# FSK_test.net
KiCad netlist of a schematic drawn in EAGLE
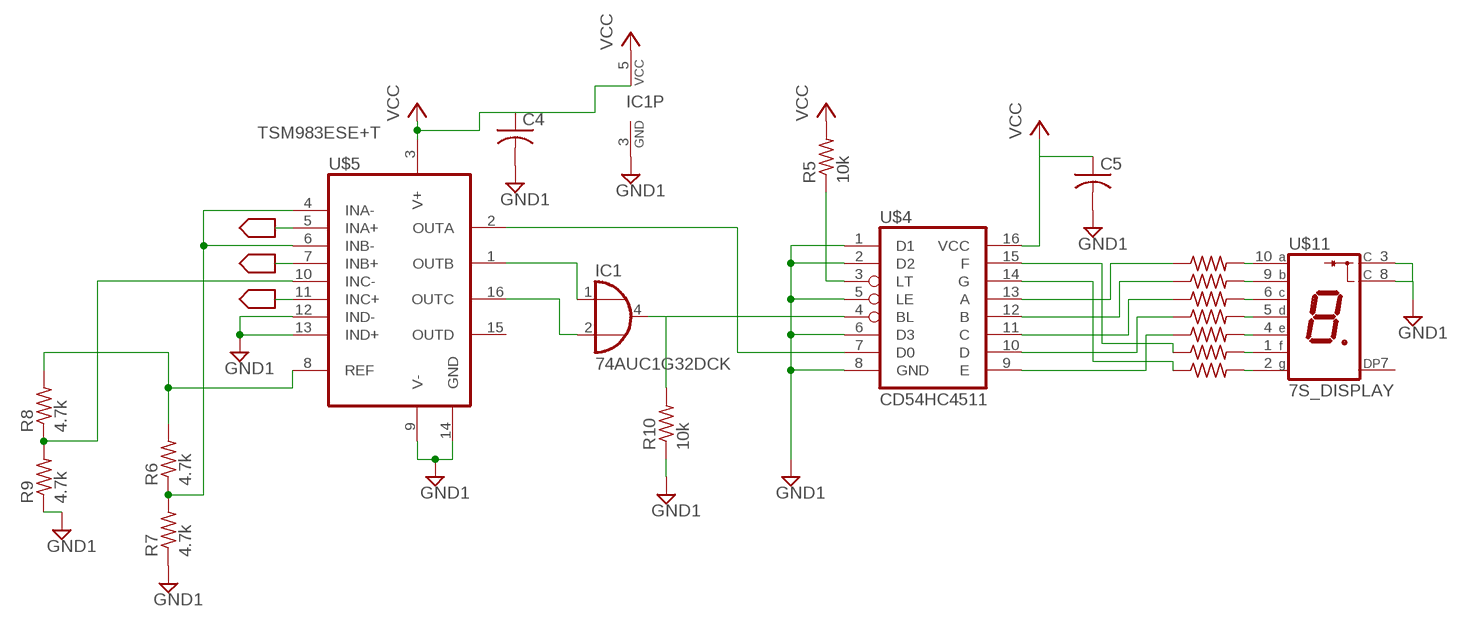
[diagram p0: schematic, sheet 1]

(export (version "E")
  (design (tool "Eeschema 10.0.6"))
  (components
    (comp (ref "C4")
      (value "C-USC0603")
      (footprint "eagle-import:C0603")
      (libsource (lib "eagle-import") (part "C-USC0603"))
    )
    (comp (ref "C5")
      (value "C-USC0603")
      (footprint "eagle-import:C0603")
      (libsource (lib "eagle-import") (part "C-USC0603"))
    )
    (comp (ref "IC1")
      (value "74AUC1G32DCK")
      (footprint "eagle-import:SC70-5")
      (libsource (lib "eagle-import") (part "741G32DCKAUC"))
    )
    (comp (ref "R5")
      (value "10k")
      (footprint "eagle-import:R1206")
      (libsource (lib "eagle-import") (part "R-US_R1206"))
    )
    (comp (ref "R6")
      (value "4.7k")
      (footprint "eagle-import:R1206")
      (libsource (lib "eagle-import") (part "R-US_R1206"))
    )
    (comp (ref "R7")
      (value "4.7k")
      (footprint "eagle-import:R1206")
      (libsource (lib "eagle-import") (part "R-US_R1206"))
    )
    (comp (ref "R8")
      (value "4.7k")
      (footprint "eagle-import:R1206")
      (libsource (lib "eagle-import") (part "R-US_R1206"))
    )
    (comp (ref "R9")
      (value "4.7k")
      (footprint "eagle-import:R1206")
      (libsource (lib "eagle-import") (part "R-US_R1206"))
    )
    (comp (ref "R10")
      (value "10k")
      (footprint "eagle-import:R1206")
      (libsource (lib "eagle-import") (part "R-US_R1206"))
    )
    (comp (ref "R11")
      (value "R-US_R0603")
      (footprint "eagle-import:R0603")
      (libsource (lib "eagle-import") (part "R-US_R0603"))
    )
    (comp (ref "R12")
      (value "R-US_R0603")
      (footprint "eagle-import:R0603")
      (libsource (lib "eagle-import") (part "R-US_R0603"))
    )
    (comp (ref "R13")
      (value "R-US_R0603")
      (footprint "eagle-import:R0603")
      (libsource (lib "eagle-import") (part "R-US_R0603"))
    )
    (comp (ref "R14")
      (value "R-US_R0603")
      (footprint "eagle-import:R0603")
      (libsource (lib "eagle-import") (part "R-US_R0603"))
    )
    (comp (ref "R15")
      (value "R-US_R0603")
      (footprint "eagle-import:R0603")
      (libsource (lib "eagle-import") (part "R-US_R0603"))
    )
    (comp (ref "R16")
      (value "R-US_R0603")
      (footprint "eagle-import:R0603")
      (libsource (lib "eagle-import") (part "R-US_R0603"))
    )
    (comp (ref "R17")
      (value "R-US_R0603")
      (footprint "eagle-import:R0603")
      (libsource (lib "eagle-import") (part "R-US_R0603"))
    )
    (comp (ref "U$4")
      (value "CD54HC4511")
      (footprint "eagle-import:CD54HC4511")
      (libsource (lib "eagle-import") (part "CD54HC4511"))
    )
    (comp (ref "U$5")
      (value "TSM983ESE+T")
      (footprint "eagle-import:TSM983ESE+T")
      (libsource (lib "eagle-import") (part "TSM983ESE+T"))
    )
    (comp (ref "U$11")
      (value "7S_DISPLAY")
      (footprint "eagle-import:7S_DISPLAY")
      (libsource (lib "eagle-import") (part "7S_DISPLAY"))
    )
  )
  (nets
    (net (code "1") (name "/2.6_OUT") (class "Default")
      (node (ref "U$5") (pin "11") (pinfunction "INC+_11") (pintype "input"))
      (node (ref "U$5") (pin "7") (pinfunction "INB+_7") (pintype "input"))
    )
    (net (code "2") (name "GND1") (class "Default")
      (node (ref "C4") (pin "2") (pinfunction "2_2") (pintype "passive"))
      (node (ref "C5") (pin "2") (pinfunction "2_2") (pintype "passive"))
      (node (ref "IC1") (pin "3") (pinfunction "GND_3") (pintype "power_in"))
      (node (ref "R10") (pin "1") (pinfunction "1_1") (pintype "passive"))
      (node (ref "R7") (pin "1") (pinfunction "1_1") (pintype "passive"))
      (node (ref "R9") (pin "1") (pinfunction "1_1") (pintype "passive"))
      (node (ref "U$11") (pin "3") (pinfunction "C_3") (pintype "passive"))
      (node (ref "U$11") (pin "8") (pinfunction "C_8") (pintype "passive"))
      (node (ref "U$4") (pin "1") (pinfunction "D1_1") (pintype "bidirectional"))
      (node (ref "U$4") (pin "2") (pinfunction "D2_2") (pintype "input"))
      (node (ref "U$4") (pin "5") (pinfunction "LE_5") (pintype "input"))
      (node (ref "U$4") (pin "6") (pinfunction "D3_6") (pintype "input"))
      (node (ref "U$4") (pin "8") (pinfunction "GND_8") (pintype "input"))
      (node (ref "U$5") (pin "12") (pinfunction "IND-_12") (pintype "input"))
      (node (ref "U$5") (pin "13") (pinfunction "IND+_13") (pintype "input"))
      (node (ref "U$5") (pin "14") (pinfunction "GND_14") (pintype "bidirectional"))
      (node (ref "U$5") (pin "9") (pinfunction "V-_9") (pintype "input"))
    )
    (net (code "3") (name "Net-(IC1A-I0)") (class "Default")
      (node (ref "IC1") (pin "1") (pinfunction "I0_1") (pintype "input"))
      (node (ref "U$5") (pin "1") (pinfunction "OUTB_1") (pintype "output"))
    )
    (net (code "4") (name "Net-(IC1A-I1)") (class "Default")
      (node (ref "IC1") (pin "2") (pinfunction "I1_2") (pintype "input"))
      (node (ref "U$5") (pin "16") (pinfunction "OUTC_16") (pintype "output"))
    )
    (net (code "5") (name "Net-(IC1A-O)") (class "Default")
      (node (ref "IC1") (pin "4") (pinfunction "O_4") (pintype "output"))
      (node (ref "R10") (pin "2") (pinfunction "2_2") (pintype "passive"))
      (node (ref "U$4") (pin "4") (pinfunction "BL_4") (pintype "input"))
    )
    (net (code "6") (name "Net-(R13-Pad2)") (class "Default")
      (node (ref "R13") (pin "2") (pinfunction "2_2") (pintype "passive"))
      (node (ref "U$11") (pin "6") (pinfunction "C_6") (pintype "passive"))
    )
    (net (code "7") (name "Net-(U$4-A)") (class "Default")
      (node (ref "R11") (pin "1") (pinfunction "1_1") (pintype "passive"))
      (node (ref "U$4") (pin "13") (pinfunction "A_13") (pintype "bidirectional"))
    )
    (net (code "8") (name "Net-(U$4-B)") (class "Default")
      (node (ref "R12") (pin "1") (pinfunction "1_1") (pintype "passive"))
      (node (ref "U$4") (pin "12") (pinfunction "B_12") (pintype "output"))
    )
    (net (code "9") (name "Net-(U$4-C)") (class "Default")
      (node (ref "R13") (pin "1") (pinfunction "1_1") (pintype "passive"))
      (node (ref "U$4") (pin "11") (pinfunction "C_11") (pintype "output"))
    )
    (net (code "10") (name "Net-(U$4-D)") (class "Default")
      (node (ref "R14") (pin "1") (pinfunction "1_1") (pintype "passive"))
      (node (ref "U$4") (pin "10") (pinfunction "D_10") (pintype "output"))
    )
    (net (code "11") (name "Net-(U$4-D0)") (class "Default")
      (node (ref "U$4") (pin "7") (pinfunction "D0_7") (pintype "input"))
      (node (ref "U$5") (pin "2") (pinfunction "OUTA_2") (pintype "output"))
    )
    (net (code "12") (name "Net-(U$4-E)") (class "Default")
      (node (ref "R15") (pin "1") (pinfunction "1_1") (pintype "passive"))
      (node (ref "U$4") (pin "9") (pinfunction "E_9") (pintype "output"))
    )
    (net (code "13") (name "Net-(U$4-F)") (class "Default")
      (node (ref "R16") (pin "1") (pinfunction "1_1") (pintype "passive"))
      (node (ref "U$4") (pin "15") (pinfunction "F_15") (pintype "output"))
    )
    (net (code "14") (name "Net-(U$4-G)") (class "Default")
      (node (ref "R17") (pin "1") (pinfunction "1_1") (pintype "passive"))
      (node (ref "U$4") (pin "14") (pinfunction "G_14") (pintype "output"))
    )
    (net (code "15") (name "Net-(U$4-LT)") (class "Default")
      (node (ref "R5") (pin "1") (pinfunction "1_1") (pintype "passive"))
      (node (ref "U$4") (pin "3") (pinfunction "LT_3") (pintype "input"))
    )
    (net (code "16") (name "Net-(U$5-INA-)") (class "Default")
      (node (ref "R6") (pin "1") (pinfunction "1_1") (pintype "passive"))
      (node (ref "R7") (pin "2") (pinfunction "2_2") (pintype "passive"))
      (node (ref "U$5") (pin "4") (pinfunction "INA-_4") (pintype "input"))
      (node (ref "U$5") (pin "6") (pinfunction "INB-_6") (pintype "input"))
    )
    (net (code "17") (name "Net-(U$5-INC-)") (class "Default")
      (node (ref "R8") (pin "1") (pinfunction "1_1") (pintype "passive"))
      (node (ref "R9") (pin "2") (pinfunction "2_2") (pintype "passive"))
      (node (ref "U$5") (pin "10") (pinfunction "INC-_10") (pintype "input"))
    )
    (net (code "18") (name "Net-(U$5-REF)") (class "Default")
      (node (ref "R6") (pin "2") (pinfunction "2_2") (pintype "passive"))
      (node (ref "R8") (pin "2") (pinfunction "2_2") (pintype "passive"))
      (node (ref "U$5") (pin "8") (pinfunction "REF_8") (pintype "input"))
    )
    (net (code "19") (name "Net-(U$11-A)") (class "Default")
      (node (ref "R11") (pin "2") (pinfunction "2_2") (pintype "passive"))
      (node (ref "U$11") (pin "10") (pinfunction "A_10") (pintype "passive"))
    )
    (net (code "20") (name "Net-(U$11-B)") (class "Default")
      (node (ref "R12") (pin "2") (pinfunction "2_2") (pintype "passive"))
      (node (ref "U$11") (pin "9") (pinfunction "B_9") (pintype "passive"))
    )
    (net (code "21") (name "Net-(U$11-D)") (class "Default")
      (node (ref "R14") (pin "2") (pinfunction "2_2") (pintype "passive"))
      (node (ref "U$11") (pin "5") (pinfunction "D_5") (pintype "passive"))
    )
    (net (code "22") (name "Net-(U$11-E)") (class "Default")
      (node (ref "R15") (pin "2") (pinfunction "2_2") (pintype "passive"))
      (node (ref "U$11") (pin "4") (pinfunction "E_4") (pintype "passive"))
    )
    (net (code "23") (name "Net-(U$11-F)") (class "Default")
      (node (ref "R16") (pin "2") (pinfunction "2_2") (pintype "passive"))
      (node (ref "U$11") (pin "1") (pinfunction "F_1") (pintype "passive"))
    )
    (net (code "24") (name "Net-(U$11-G)") (class "Default")
      (node (ref "R17") (pin "2") (pinfunction "2_2") (pintype "passive"))
      (node (ref "U$11") (pin "2") (pinfunction "G_2") (pintype "passive"))
    )
    (net (code "25") (name "VCC") (class "Default")
      (node (ref "C4") (pin "1") (pinfunction "1_1") (pintype "passive"))
      (node (ref "C5") (pin "1") (pinfunction "1_1") (pintype "passive"))
      (node (ref "IC1") (pin "5") (pinfunction "VCC_5") (pintype "power_in"))
      (node (ref "R5") (pin "2") (pinfunction "2_2") (pintype "passive"))
      (node (ref "U$4") (pin "16") (pinfunction "VCC_16") (pintype "output"))
      (node (ref "U$5") (pin "3") (pinfunction "V+_3") (pintype "input"))
    )
    (net (code "26") (name "unconnected-(U$5-INA+-Pad5)") (class "Default")
      (node (ref "U$5") (pin "5") (pinfunction "INA+_5") (pintype "input"))
    )
    (net (code "27") (name "unconnected-(U$5-OUTD-Pad15)") (class "Default")
      (node (ref "U$5") (pin "15") (pinfunction "OUTD_15") (pintype "bidirectional"))
    )
    (net (code "28") (name "unconnected-(U$11-DP-Pad7)") (class "Default")
      (node (ref "U$11") (pin "7") (pinfunction "DP_7") (pintype "passive"))
    )
  )
)
